# DIDO.net
KiCad netlist of a schematic drawn in Altium Designer
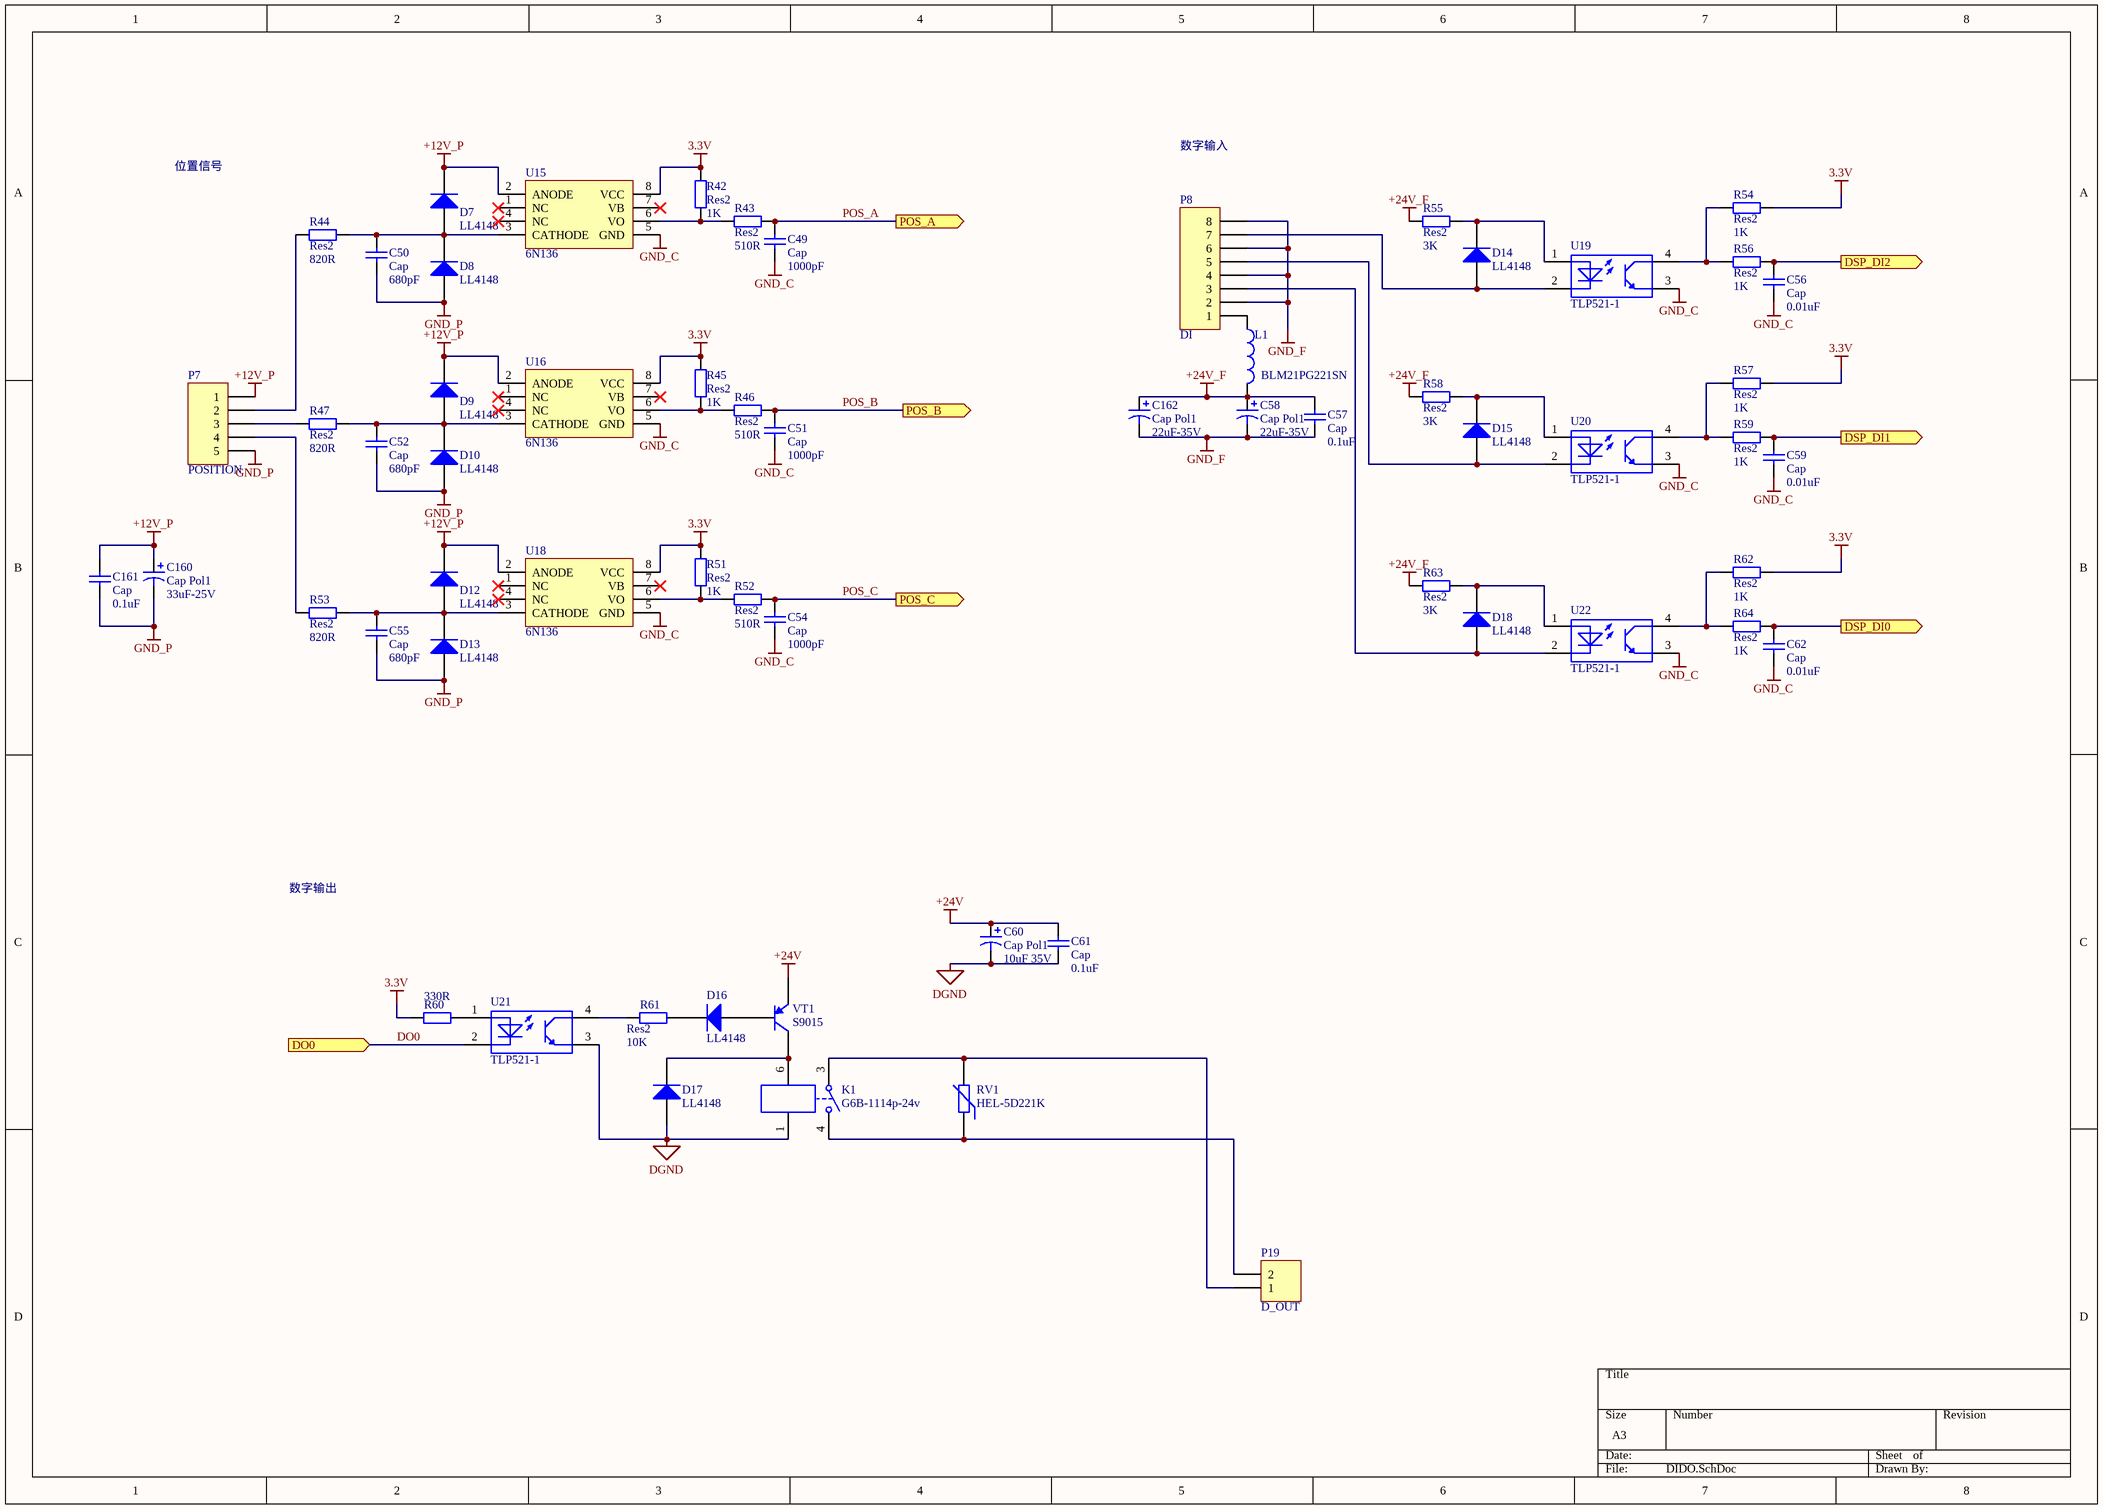
[diagram p0: DIDO.SchDoc]

(export (version "E")
  (design (tool "Eeschema 10.0.6"))
  (components
    (comp (ref "C49")
      (value "Cap")
      (footprint "1206")
      (description "Capacitor")
      (fields (field (name "ALTIUM_VALUE") "1000pF") (field (name "PUBLISHER") "Altium Limited"))
      (libsource (lib "Miscellaneous Devices") (part "Cap"))
    )
    (comp (ref "C50")
      (value "Cap")
      (footprint "1206")
      (description "Capacitor")
      (fields (field (name "ALTIUM_VALUE") "680pF") (field (name "PUBLISHER") "Altium Limited"))
      (libsource (lib "Miscellaneous Devices") (part "Cap"))
    )
    (comp (ref "C51")
      (value "Cap")
      (footprint "1206")
      (description "Capacitor")
      (fields (field (name "ALTIUM_VALUE") "1000pF") (field (name "PUBLISHER") "Altium Limited"))
      (libsource (lib "Miscellaneous Devices") (part "Cap"))
    )
    (comp (ref "C52")
      (value "Cap")
      (footprint "1206")
      (description "Capacitor")
      (fields (field (name "ALTIUM_VALUE") "680pF") (field (name "PUBLISHER") "Altium Limited"))
      (libsource (lib "Miscellaneous Devices") (part "Cap"))
    )
    (comp (ref "C54")
      (value "Cap")
      (footprint "1206")
      (description "Capacitor")
      (fields (field (name "ALTIUM_VALUE") "1000pF") (field (name "PUBLISHER") "Altium Limited"))
      (libsource (lib "Miscellaneous Devices") (part "Cap"))
    )
    (comp (ref "C55")
      (value "Cap")
      (footprint "1206")
      (description "Capacitor")
      (fields (field (name "ALTIUM_VALUE") "680pF") (field (name "PUBLISHER") "Altium Limited"))
      (libsource (lib "Miscellaneous Devices") (part "Cap"))
    )
    (comp (ref "C56")
      (value "Cap")
      (footprint "1206")
      (description "Capacitor")
      (fields (field (name "ALTIUM_VALUE") "0.01uF") (field (name "PUBLISHER") "Altium Limited"))
      (libsource (lib "Miscellaneous Devices") (part "Cap"))
    )
    (comp (ref "C57")
      (value "Cap")
      (footprint "1206")
      (description "Capacitor")
      (fields (field (name "ALTIUM_VALUE") "0.1uF") (field (name "PUBLISHER") "Altium Limited"))
      (libsource (lib "Miscellaneous Devices") (part "Cap"))
    )
    (comp (ref "C58")
      (value "Cap Pol1")
      (footprint "7343")
      (description "Polarized Capacitor (Radial)")
      (fields (field (name "ALTIUM_VALUE") "22uF-35V") (field (name "PUBLISHER") "Altium Limited"))
      (libsource (lib "Miscellaneous Devices") (part "Cap Pol1"))
    )
    (comp (ref "C59")
      (value "Cap")
      (footprint "1206")
      (description "Capacitor")
      (fields (field (name "ALTIUM_VALUE") "0.01uF") (field (name "PUBLISHER") "Altium Limited"))
      (libsource (lib "Miscellaneous Devices") (part "Cap"))
    )
    (comp (ref "C60")
      (value "Cap Pol1")
      (footprint "7343")
      (description "Polarized Capacitor (Radial)")
      (fields (field (name "ALTIUM_VALUE") "10uF 35V") (field (name "PUBLISHER") "Altium Limited"))
      (libsource (lib "Miscellaneous Devices") (part "Cap Pol1"))
    )
    (comp (ref "C61")
      (value "Cap")
      (footprint "1206")
      (description "Capacitor")
      (fields (field (name "ALTIUM_VALUE") "0.1uF") (field (name "PUBLISHER") "Altium Limited"))
      (libsource (lib "Miscellaneous Devices") (part "Cap"))
    )
    (comp (ref "C62")
      (value "Cap")
      (footprint "1206")
      (description "Capacitor")
      (fields (field (name "ALTIUM_VALUE") "0.01uF") (field (name "PUBLISHER") "Altium Limited"))
      (libsource (lib "Miscellaneous Devices") (part "Cap"))
    )
    (comp (ref "C160")
      (value "Cap Pol1")
      (footprint "7343")
      (description "Polarized Capacitor (Radial)")
      (fields (field (name "ALTIUM_VALUE") "33uF-25V") (field (name "PUBLISHER") "Altium Limited"))
      (libsource (lib "Miscellaneous Devices") (part "Cap Pol1"))
    )
    (comp (ref "C161")
      (value "Cap")
      (footprint "1206")
      (description "Capacitor")
      (fields (field (name "ALTIUM_VALUE") "0.1uF") (field (name "PUBLISHER") "Altium Limited"))
      (libsource (lib "Miscellaneous Devices") (part "Cap"))
    )
    (comp (ref "C162")
      (value "Cap Pol1")
      (footprint "7343")
      (description "Polarized Capacitor (Radial)")
      (fields (field (name "ALTIUM_VALUE") "22uF-35V") (field (name "PUBLISHER") "Altium Limited"))
      (libsource (lib "Miscellaneous Devices") (part "Cap Pol1"))
    )
    (comp (ref "D7")
      (value "LL4148")
      (footprint "SOD-80/MLL34")
      (description "High Conductance Fast Diode")
      (fields (field (name "PUBLISHER") "Altium Limited"))
      (libsource (lib "Miscellaneous Devices") (part "Diode 1N4148"))
    )
    (comp (ref "D8")
      (value "LL4148")
      (footprint "SOD-80/MLL34")
      (description "High Conductance Fast Diode")
      (fields (field (name "PUBLISHER") "Altium Limited"))
      (libsource (lib "Miscellaneous Devices") (part "Diode 1N4148"))
    )
    (comp (ref "D9")
      (value "LL4148")
      (footprint "SOD-80/MLL34")
      (description "High Conductance Fast Diode")
      (fields (field (name "PUBLISHER") "Altium Limited"))
      (libsource (lib "Miscellaneous Devices") (part "Diode 1N4148"))
    )
    (comp (ref "D10")
      (value "LL4148")
      (footprint "SOD-80/MLL34")
      (description "High Conductance Fast Diode")
      (fields (field (name "PUBLISHER") "Altium Limited"))
      (libsource (lib "Miscellaneous Devices") (part "Diode 1N4148"))
    )
    (comp (ref "D12")
      (value "LL4148")
      (footprint "SOD-80/MLL34")
      (description "High Conductance Fast Diode")
      (fields (field (name "PUBLISHER") "Altium Limited"))
      (libsource (lib "Miscellaneous Devices") (part "Diode 1N4148"))
    )
    (comp (ref "D13")
      (value "LL4148")
      (footprint "SOD-80/MLL34")
      (description "High Conductance Fast Diode")
      (fields (field (name "PUBLISHER") "Altium Limited"))
      (libsource (lib "Miscellaneous Devices") (part "Diode 1N4148"))
    )
    (comp (ref "D14")
      (value "LL4148")
      (footprint "SOD-80/MLL34")
      (description "1 Amp General Purpose Rectifier")
      (fields (field (name "PUBLISHER") "Altium Limited"))
      (libsource (lib "Miscellaneous Devices") (part "Diode 1N4007"))
    )
    (comp (ref "D15")
      (value "LL4148")
      (footprint "SOD-80/MLL34")
      (description "1 Amp General Purpose Rectifier")
      (fields (field (name "PUBLISHER") "Altium Limited"))
      (libsource (lib "Miscellaneous Devices") (part "Diode 1N4007"))
    )
    (comp (ref "D16")
      (value "LL4148")
      (footprint "SOD-80/MLL34")
      (description "High Conductance Fast Diode")
      (fields (field (name "PUBLISHER") "Altium Limited"))
      (libsource (lib "Miscellaneous Devices") (part "Diode 1N4148"))
    )
    (comp (ref "D17")
      (value "LL4148")
      (footprint "SOD-80/MLL34")
      (description "1 Amp General Purpose Rectifier")
      (fields (field (name "PUBLISHER") "Altium Limited"))
      (libsource (lib "Miscellaneous Devices") (part "Diode 1N4007"))
    )
    (comp (ref "D18")
      (value "LL4148")
      (footprint "SOD-80/MLL34")
      (description "1 Amp General Purpose Rectifier")
      (fields (field (name "PUBLISHER") "Altium Limited"))
      (libsource (lib "Miscellaneous Devices") (part "Diode 1N4007"))
    )
    (comp (ref "K1")
      (value "G6B-1114p-24v")
      (footprint "SPST-NO")
      (description "Single-Pole Single-Throw Relay")
      (fields (field (name "PUBLISHER") "Altium Limited"))
      (libsource (lib "Miscellaneous Devices") (part "Relay-SPST"))
    )
    (comp (ref "L1")
      (value "BLM21PG221SN")
      (footprint "2012")
      (description "Inductor")
      (fields (field (name "PUBLISHER") "Altium Limited"))
      (libsource (lib "Miscellaneous Devices") (part "Inductor"))
    )
    (comp (ref "P7")
      (value "POSITION")
      (footprint "phenox-5")
      (description "Header, 5-Pin")
      (fields (field (name "PUBLISHER") "Altium Limited"))
      (libsource (lib "Miscellaneous Connectors") (part "Header 5"))
    )
    (comp (ref "P8")
      (value "DI")
      (footprint "PCB21:phenox-8")
      (description "Header, 8-Pin")
      (fields (field (name "PUBLISHER") "Altium Limited"))
      (libsource (lib "Miscellaneous Connectors") (part "Header 8"))
    )
    (comp (ref "P19")
      (value "D_OUT")
      (footprint "phenox-2")
      (description "Header, 2-Pin")
      (fields (field (name "PUBLISHER") "Altium Limited"))
      (libsource (lib "Miscellaneous Connectors") (part "Header 2"))
    )
    (comp (ref "R42")
      (value "Res2")
      (footprint "1206")
      (description "Resistor")
      (fields (field (name "ALTIUM_VALUE") "1K") (field (name "PUBLISHER") "Altium Limited"))
      (libsource (lib "") (part "Res2_1"))
    )
    (comp (ref "R43")
      (value "Res2")
      (footprint "1206")
      (description "Resistor")
      (fields (field (name "ALTIUM_VALUE") "510R") (field (name "PUBLISHER") "Altium Limited"))
      (libsource (lib "Miscellaneous Devices") (part "Res2"))
    )
    (comp (ref "R44")
      (value "Res2")
      (footprint "1206")
      (description "Resistor")
      (fields (field (name "ALTIUM_VALUE") "820R") (field (name "PUBLISHER") "Altium Limited"))
      (libsource (lib "Miscellaneous Devices") (part "Res2"))
    )
    (comp (ref "R45")
      (value "Res2")
      (footprint "1206")
      (description "Resistor")
      (fields (field (name "ALTIUM_VALUE") "1K") (field (name "PUBLISHER") "Altium Limited"))
      (libsource (lib "") (part "Res2_1"))
    )
    (comp (ref "R46")
      (value "Res2")
      (footprint "1206")
      (description "Resistor")
      (fields (field (name "ALTIUM_VALUE") "510R") (field (name "PUBLISHER") "Altium Limited"))
      (libsource (lib "Miscellaneous Devices") (part "Res2"))
    )
    (comp (ref "R47")
      (value "Res2")
      (footprint "1206")
      (description "Resistor")
      (fields (field (name "ALTIUM_VALUE") "820R") (field (name "PUBLISHER") "Altium Limited"))
      (libsource (lib "Miscellaneous Devices") (part "Res2"))
    )
    (comp (ref "R51")
      (value "Res2")
      (footprint "1206")
      (description "Resistor")
      (fields (field (name "ALTIUM_VALUE") "1K") (field (name "PUBLISHER") "Altium Limited"))
      (libsource (lib "") (part "Res2_1"))
    )
    (comp (ref "R52")
      (value "Res2")
      (footprint "1206")
      (description "Resistor")
      (fields (field (name "ALTIUM_VALUE") "510R") (field (name "PUBLISHER") "Altium Limited"))
      (libsource (lib "Miscellaneous Devices") (part "Res2"))
    )
    (comp (ref "R53")
      (value "Res2")
      (footprint "1206")
      (description "Resistor")
      (fields (field (name "ALTIUM_VALUE") "820R") (field (name "PUBLISHER") "Altium Limited"))
      (libsource (lib "Miscellaneous Devices") (part "Res2"))
    )
    (comp (ref "R54")
      (value "Res2")
      (footprint "1206")
      (description "Resistor")
      (fields (field (name "ALTIUM_VALUE") "1K") (field (name "PUBLISHER") "Altium Limited"))
      (libsource (lib "Miscellaneous Devices") (part "Res2"))
    )
    (comp (ref "R55")
      (value "Res2")
      (footprint "1206")
      (description "Resistor")
      (fields (field (name "ALTIUM_VALUE") "3K") (field (name "PUBLISHER") "Altium Limited"))
      (libsource (lib "Miscellaneous Devices") (part "Res2"))
    )
    (comp (ref "R56")
      (value "Res2")
      (footprint "1206")
      (description "Resistor")
      (fields (field (name "ALTIUM_VALUE") "1K") (field (name "PUBLISHER") "Altium Limited"))
      (libsource (lib "Miscellaneous Devices") (part "Res2"))
    )
    (comp (ref "R57")
      (value "Res2")
      (footprint "1206")
      (description "Resistor")
      (fields (field (name "ALTIUM_VALUE") "1K") (field (name "PUBLISHER") "Altium Limited"))
      (libsource (lib "Miscellaneous Devices") (part "Res2"))
    )
    (comp (ref "R58")
      (value "Res2")
      (footprint "1206")
      (description "Resistor")
      (fields (field (name "ALTIUM_VALUE") "3K") (field (name "PUBLISHER") "Altium Limited"))
      (libsource (lib "Miscellaneous Devices") (part "Res2"))
    )
    (comp (ref "R59")
      (value "Res2")
      (footprint "1206")
      (description "Resistor")
      (fields (field (name "ALTIUM_VALUE") "1K") (field (name "PUBLISHER") "Altium Limited"))
      (libsource (lib "Miscellaneous Devices") (part "Res2"))
    )
    (comp (ref "R60")
      (value "330R")
      (footprint "1206")
      (description "Resistor")
      (fields (field (name "Comment") "Res2") (field (name "PUBLISHER") "Altium Limited"))
      (libsource (lib "Miscellaneous Devices") (part "Res2"))
    )
    (comp (ref "R61")
      (value "Res2")
      (footprint "1206")
      (description "Resistor")
      (fields (field (name "ALTIUM_VALUE") "10K") (field (name "PUBLISHER") "Altium Limited"))
      (libsource (lib "Miscellaneous Devices") (part "Res2"))
    )
    (comp (ref "R62")
      (value "Res2")
      (footprint "1206")
      (description "Resistor")
      (fields (field (name "ALTIUM_VALUE") "1K") (field (name "PUBLISHER") "Altium Limited"))
      (libsource (lib "Miscellaneous Devices") (part "Res2"))
    )
    (comp (ref "R63")
      (value "Res2")
      (footprint "1206")
      (description "Resistor")
      (fields (field (name "ALTIUM_VALUE") "3K") (field (name "PUBLISHER") "Altium Limited"))
      (libsource (lib "Miscellaneous Devices") (part "Res2"))
    )
    (comp (ref "R64")
      (value "Res2")
      (footprint "1206")
      (description "Resistor")
      (fields (field (name "ALTIUM_VALUE") "1K") (field (name "PUBLISHER") "Altium Limited"))
      (libsource (lib "Miscellaneous Devices") (part "Res2"))
    )
    (comp (ref "RV1")
      (value "HEL-5D221K")
      (footprint "RAD-0.2")
      (libsource (lib "Schlib1") (part "HEL-5D221K"))
    )
    (comp (ref "U15")
      (value "6N136")
      (footprint "DIP-8N")
      (description "光耦")
      (libsource (lib "Integrated_Library1") (part "6N136"))
    )
    (comp (ref "U16")
      (value "6N136")
      (footprint "DIP-8N")
      (description "光耦")
      (libsource (lib "Integrated_Library1") (part "6N136"))
    )
    (comp (ref "U18")
      (value "6N136")
      (footprint "DIP-8N")
      (description "光耦")
      (libsource (lib "Integrated_Library1") (part "6N136"))
    )
    (comp (ref "U19")
      (value "TLP521-1")
      (footprint "DIP4")
      (libsource (lib "Integrated_Library1") (part "TLP521-1"))
    )
    (comp (ref "U20")
      (value "TLP521-1")
      (footprint "DIP4")
      (libsource (lib "Integrated_Library1") (part "TLP521-1"))
    )
    (comp (ref "U21")
      (value "TLP521-1")
      (footprint "DIP4")
      (libsource (lib "Integrated_Library1") (part "TLP521-1"))
    )
    (comp (ref "U22")
      (value "TLP521-1")
      (footprint "DIP4")
      (libsource (lib "Integrated_Library1") (part "TLP521-1"))
    )
    (comp (ref "VT1") (value "S9015") (footprint "SOT23") (libsource (lib "Schlib2") (part "S9015")))
  )
  (nets
    (net (code "1") (name "+12V_P") (class "Default")
      (node (ref "C160") (pin "1") (pinfunction "1_1") (pintype "passive"))
      (node (ref "C161") (pin "2") (pinfunction "2_2") (pintype "passive"))
      (node (ref "D12") (pin "2") (pinfunction "K_2") (pintype "passive"))
      (node (ref "D7") (pin "2") (pinfunction "K_2") (pintype "passive"))
      (node (ref "D9") (pin "2") (pinfunction "K_2") (pintype "passive"))
      (node (ref "P7") (pin "1") (pinfunction "1_1") (pintype "passive"))
      (node (ref "U15") (pin "2") (pinfunction "ANODE_2") (pintype "passive"))
      (node (ref "U16") (pin "2") (pinfunction "ANODE_2") (pintype "passive"))
      (node (ref "U18") (pin "2") (pinfunction "ANODE_2") (pintype "passive"))
    )
    (net (code "2") (name "+24V") (class "Default")
      (node (ref "C60") (pin "1") (pinfunction "1_1") (pintype "passive"))
      (node (ref "C61") (pin "2") (pinfunction "2_2") (pintype "passive"))
      (node (ref "VT1") (pin "3") (pinfunction "3_3") (pintype "passive"))
    )
    (net (code "3") (name "+24V_F") (class "Default")
      (node (ref "C162") (pin "1") (pinfunction "1_1") (pintype "passive"))
      (node (ref "C57") (pin "2") (pinfunction "2_2") (pintype "passive"))
      (node (ref "C58") (pin "1") (pinfunction "1_1") (pintype "passive"))
      (node (ref "L1") (pin "2") (pinfunction "2_2") (pintype "passive"))
      (node (ref "R55") (pin "1") (pinfunction "1_1") (pintype "passive"))
      (node (ref "R58") (pin "1") (pinfunction "1_1") (pintype "passive"))
      (node (ref "R63") (pin "1") (pinfunction "1_1") (pintype "passive"))
    )
    (net (code "4") (name "/DO0") (class "Default")
      (node (ref "U21") (pin "2") (pinfunction "2_2") (pintype "passive"))
    )
    (net (code "5") (name "/DSP_DI0") (class "Default")
      (node (ref "C62") (pin "2") (pinfunction "2_2") (pintype "passive"))
      (node (ref "R64") (pin "2") (pinfunction "2_2") (pintype "passive"))
    )
    (net (code "6") (name "/DSP_DI1") (class "Default")
      (node (ref "C59") (pin "2") (pinfunction "2_2") (pintype "passive"))
      (node (ref "R59") (pin "2") (pinfunction "2_2") (pintype "passive"))
    )
    (net (code "7") (name "/DSP_DI2") (class "Default")
      (node (ref "C56") (pin "2") (pinfunction "2_2") (pintype "passive"))
      (node (ref "R56") (pin "2") (pinfunction "2_2") (pintype "passive"))
    )
    (net (code "8") (name "/POS_A") (class "Default")
      (node (ref "C49") (pin "2") (pinfunction "2_2") (pintype "passive"))
      (node (ref "R43") (pin "2") (pinfunction "2_2") (pintype "passive"))
    )
    (net (code "9") (name "/POS_B") (class "Default")
      (node (ref "C51") (pin "2") (pinfunction "2_2") (pintype "passive"))
      (node (ref "R46") (pin "2") (pinfunction "2_2") (pintype "passive"))
    )
    (net (code "10") (name "/POS_C") (class "Default")
      (node (ref "C54") (pin "2") (pinfunction "2_2") (pintype "passive"))
      (node (ref "R52") (pin "2") (pinfunction "2_2") (pintype "passive"))
    )
    (net (code "11") (name "3.3V") (class "Default")
      (node (ref "R42") (pin "2") (pinfunction "2_2") (pintype "passive"))
      (node (ref "R45") (pin "2") (pinfunction "2_2") (pintype "passive"))
      (node (ref "R51") (pin "2") (pinfunction "2_2") (pintype "passive"))
      (node (ref "R54") (pin "2") (pinfunction "2_2") (pintype "passive"))
      (node (ref "R57") (pin "2") (pinfunction "2_2") (pintype "passive"))
      (node (ref "R60") (pin "1") (pinfunction "1_1") (pintype "passive"))
      (node (ref "R62") (pin "2") (pinfunction "2_2") (pintype "passive"))
      (node (ref "U15") (pin "8") (pinfunction "VCC_8") (pintype "power_in"))
      (node (ref "U16") (pin "8") (pinfunction "VCC_8") (pintype "power_in"))
      (node (ref "U18") (pin "8") (pinfunction "VCC_8") (pintype "power_in"))
    )
    (net (code "12") (name "DGND") (class "Default")
      (node (ref "C60") (pin "2") (pinfunction "2_2") (pintype "passive"))
      (node (ref "C61") (pin "1") (pinfunction "1_1") (pintype "passive"))
      (node (ref "D17") (pin "1") (pinfunction "A_1") (pintype "passive"))
      (node (ref "K1") (pin "1") (pinfunction "1_1") (pintype "passive"))
      (node (ref "U21") (pin "3") (pinfunction "3_3") (pintype "passive"))
    )
    (net (code "13") (name "GND_C") (class "Default")
      (node (ref "C49") (pin "1") (pinfunction "1_1") (pintype "passive"))
      (node (ref "C51") (pin "1") (pinfunction "1_1") (pintype "passive"))
      (node (ref "C54") (pin "1") (pinfunction "1_1") (pintype "passive"))
      (node (ref "C56") (pin "1") (pinfunction "1_1") (pintype "passive"))
      (node (ref "C59") (pin "1") (pinfunction "1_1") (pintype "passive"))
      (node (ref "C62") (pin "1") (pinfunction "1_1") (pintype "passive"))
      (node (ref "U15") (pin "5") (pinfunction "GND_5") (pintype "passive"))
      (node (ref "U16") (pin "5") (pinfunction "GND_5") (pintype "passive"))
      (node (ref "U18") (pin "5") (pinfunction "GND_5") (pintype "passive"))
      (node (ref "U19") (pin "3") (pinfunction "3_3") (pintype "passive"))
      (node (ref "U20") (pin "3") (pinfunction "3_3") (pintype "passive"))
      (node (ref "U22") (pin "3") (pinfunction "3_3") (pintype "passive"))
    )
    (net (code "14") (name "GND_F") (class "Default")
      (node (ref "C162") (pin "2") (pinfunction "2_2") (pintype "passive"))
      (node (ref "C57") (pin "1") (pinfunction "1_1") (pintype "passive"))
      (node (ref "C58") (pin "2") (pinfunction "2_2") (pintype "passive"))
      (node (ref "P8") (pin "2") (pinfunction "2_2") (pintype "passive"))
      (node (ref "P8") (pin "4") (pinfunction "4_4") (pintype "passive"))
      (node (ref "P8") (pin "6") (pinfunction "6_6") (pintype "passive"))
      (node (ref "P8") (pin "8") (pinfunction "8_8") (pintype "passive"))
    )
    (net (code "15") (name "GND_P") (class "Default")
      (node (ref "C160") (pin "2") (pinfunction "2_2") (pintype "passive"))
      (node (ref "C161") (pin "1") (pinfunction "1_1") (pintype "passive"))
      (node (ref "C50") (pin "1") (pinfunction "1_1") (pintype "passive"))
      (node (ref "C52") (pin "1") (pinfunction "1_1") (pintype "passive"))
      (node (ref "C55") (pin "1") (pinfunction "1_1") (pintype "passive"))
      (node (ref "D10") (pin "1") (pinfunction "A_1") (pintype "passive"))
      (node (ref "D13") (pin "1") (pinfunction "A_1") (pintype "passive"))
      (node (ref "D8") (pin "1") (pinfunction "A_1") (pintype "passive"))
      (node (ref "P7") (pin "5") (pinfunction "5_5") (pintype "passive"))
    )
    (net (code "16") (name "Net-(D7-A)") (class "Default")
      (node (ref "C50") (pin "2") (pinfunction "2_2") (pintype "passive"))
      (node (ref "D7") (pin "1") (pinfunction "A_1") (pintype "passive"))
      (node (ref "D8") (pin "2") (pinfunction "K_2") (pintype "passive"))
      (node (ref "R44") (pin "2") (pinfunction "2_2") (pintype "passive"))
      (node (ref "U15") (pin "3") (pinfunction "CATHODE_3") (pintype "passive"))
    )
    (net (code "17") (name "Net-(D10-K)") (class "Default")
      (node (ref "C52") (pin "2") (pinfunction "2_2") (pintype "passive"))
      (node (ref "D10") (pin "2") (pinfunction "K_2") (pintype "passive"))
      (node (ref "D9") (pin "1") (pinfunction "A_1") (pintype "passive"))
      (node (ref "R47") (pin "2") (pinfunction "2_2") (pintype "passive"))
      (node (ref "U16") (pin "3") (pinfunction "CATHODE_3") (pintype "passive"))
    )
    (net (code "18") (name "Net-(D12-A)") (class "Default")
      (node (ref "C55") (pin "2") (pinfunction "2_2") (pintype "passive"))
      (node (ref "D12") (pin "1") (pinfunction "A_1") (pintype "passive"))
      (node (ref "D13") (pin "2") (pinfunction "K_2") (pintype "passive"))
      (node (ref "R53") (pin "2") (pinfunction "2_2") (pintype "passive"))
      (node (ref "U18") (pin "3") (pinfunction "CATHODE_3") (pintype "passive"))
    )
    (net (code "19") (name "Net-(D14-A)") (class "Default")
      (node (ref "D14") (pin "1") (pinfunction "A_1") (pintype "passive"))
      (node (ref "P8") (pin "7") (pinfunction "7_7") (pintype "passive"))
      (node (ref "U19") (pin "2") (pinfunction "2_2") (pintype "passive"))
    )
    (net (code "20") (name "Net-(D14-K)") (class "Default")
      (node (ref "D14") (pin "2") (pinfunction "K_2") (pintype "passive"))
      (node (ref "R55") (pin "2") (pinfunction "2_2") (pintype "passive"))
      (node (ref "U19") (pin "1") (pinfunction "1_1") (pintype "passive"))
    )
    (net (code "21") (name "Net-(D15-A)") (class "Default")
      (node (ref "D15") (pin "1") (pinfunction "A_1") (pintype "passive"))
      (node (ref "P8") (pin "5") (pinfunction "5_5") (pintype "passive"))
      (node (ref "U20") (pin "2") (pinfunction "2_2") (pintype "passive"))
    )
    (net (code "22") (name "Net-(D15-K)") (class "Default")
      (node (ref "D15") (pin "2") (pinfunction "K_2") (pintype "passive"))
      (node (ref "R58") (pin "2") (pinfunction "2_2") (pintype "passive"))
      (node (ref "U20") (pin "1") (pinfunction "1_1") (pintype "passive"))
    )
    (net (code "23") (name "Net-(D16-A)") (class "Default")
      (node (ref "D16") (pin "1") (pinfunction "A_1") (pintype "passive"))
      (node (ref "VT1") (pin "2") (pinfunction "2_2") (pintype "passive"))
    )
    (net (code "24") (name "Net-(D16-K)") (class "Default")
      (node (ref "D16") (pin "2") (pinfunction "K_2") (pintype "passive"))
      (node (ref "R61") (pin "2") (pinfunction "2_2") (pintype "passive"))
    )
    (net (code "25") (name "Net-(D17-K)") (class "Default")
      (node (ref "D17") (pin "2") (pinfunction "K_2") (pintype "passive"))
      (node (ref "K1") (pin "6") (pinfunction "6_6") (pintype "passive"))
      (node (ref "VT1") (pin "1") (pinfunction "1_1") (pintype "passive"))
    )
    (net (code "26") (name "Net-(D18-A)") (class "Default")
      (node (ref "D18") (pin "1") (pinfunction "A_1") (pintype "passive"))
      (node (ref "P8") (pin "3") (pinfunction "3_3") (pintype "passive"))
      (node (ref "U22") (pin "2") (pinfunction "2_2") (pintype "passive"))
    )
    (net (code "27") (name "Net-(D18-K)") (class "Default")
      (node (ref "D18") (pin "2") (pinfunction "K_2") (pintype "passive"))
      (node (ref "R63") (pin "2") (pinfunction "2_2") (pintype "passive"))
      (node (ref "U22") (pin "1") (pinfunction "1_1") (pintype "passive"))
    )
    (net (code "28") (name "Net-(K1-Pad3)") (class "Default")
      (node (ref "K1") (pin "3") (pinfunction "3_3") (pintype "passive"))
      (node (ref "P19") (pin "1") (pinfunction "1_1") (pintype "passive"))
      (node (ref "RV1") (pin "2") (pinfunction "2_2") (pintype "passive"))
    )
    (net (code "29") (name "Net-(K1-Pad4)") (class "Default")
      (node (ref "K1") (pin "4") (pinfunction "4_4") (pintype "passive"))
      (node (ref "P19") (pin "2") (pinfunction "2_2") (pintype "passive"))
      (node (ref "RV1") (pin "1") (pinfunction "1_1") (pintype "passive"))
    )
    (net (code "30") (name "Net-(L1-Pad1)") (class "Default")
      (node (ref "L1") (pin "1") (pinfunction "1_1") (pintype "passive"))
      (node (ref "P8") (pin "1") (pinfunction "1_1") (pintype "passive"))
    )
    (net (code "31") (name "Net-(P7-Pad2)") (class "Default")
      (node (ref "P7") (pin "2") (pinfunction "2_2") (pintype "passive"))
      (node (ref "R44") (pin "1") (pinfunction "1_1") (pintype "passive"))
    )
    (net (code "32") (name "Net-(P7-Pad3)") (class "Default")
      (node (ref "P7") (pin "3") (pinfunction "3_3") (pintype "passive"))
      (node (ref "R47") (pin "1") (pinfunction "1_1") (pintype "passive"))
    )
    (net (code "33") (name "Net-(P7-Pad4)") (class "Default")
      (node (ref "P7") (pin "4") (pinfunction "4_4") (pintype "passive"))
      (node (ref "R53") (pin "1") (pinfunction "1_1") (pintype "passive"))
    )
    (net (code "34") (name "Net-(R54-Pad1)") (class "Default")
      (node (ref "R54") (pin "1") (pinfunction "1_1") (pintype "passive"))
      (node (ref "R56") (pin "1") (pinfunction "1_1") (pintype "passive"))
      (node (ref "U19") (pin "4") (pinfunction "4_4") (pintype "passive"))
    )
    (net (code "35") (name "Net-(R57-Pad1)") (class "Default")
      (node (ref "R57") (pin "1") (pinfunction "1_1") (pintype "passive"))
      (node (ref "R59") (pin "1") (pinfunction "1_1") (pintype "passive"))
      (node (ref "U20") (pin "4") (pinfunction "4_4") (pintype "passive"))
    )
    (net (code "36") (name "Net-(R60-Pad2)") (class "Default")
      (node (ref "R60") (pin "2") (pinfunction "2_2") (pintype "passive"))
      (node (ref "U21") (pin "1") (pinfunction "1_1") (pintype "passive"))
    )
    (net (code "37") (name "Net-(R61-Pad1)") (class "Default")
      (node (ref "R61") (pin "1") (pinfunction "1_1") (pintype "passive"))
      (node (ref "U21") (pin "4") (pinfunction "4_4") (pintype "passive"))
    )
    (net (code "38") (name "Net-(R62-Pad1)") (class "Default")
      (node (ref "R62") (pin "1") (pinfunction "1_1") (pintype "passive"))
      (node (ref "R64") (pin "1") (pinfunction "1_1") (pintype "passive"))
      (node (ref "U22") (pin "4") (pinfunction "4_4") (pintype "passive"))
    )
    (net (code "39") (name "Net-(U15-VO)") (class "Default")
      (node (ref "R42") (pin "1") (pinfunction "1_1") (pintype "passive"))
      (node (ref "R43") (pin "1") (pinfunction "1_1") (pintype "passive"))
      (node (ref "U15") (pin "6") (pinfunction "VO_6") (pintype "passive"))
    )
    (net (code "40") (name "Net-(U16-VO)") (class "Default")
      (node (ref "R45") (pin "1") (pinfunction "1_1") (pintype "passive"))
      (node (ref "R46") (pin "1") (pinfunction "1_1") (pintype "passive"))
      (node (ref "U16") (pin "6") (pinfunction "VO_6") (pintype "passive"))
    )
    (net (code "41") (name "Net-(U18-VO)") (class "Default")
      (node (ref "R51") (pin "1") (pinfunction "1_1") (pintype "passive"))
      (node (ref "R52") (pin "1") (pinfunction "1_1") (pintype "passive"))
      (node (ref "U18") (pin "6") (pinfunction "VO_6") (pintype "passive"))
    )
    (net (code "42") (name "unconnected-(U15-NC-Pad1)") (class "Default")
      (node (ref "U15") (pin "1") (pinfunction "NC_1") (pintype "passive+no_connect"))
    )
    (net (code "43") (name "unconnected-(U15-NC-Pad4)") (class "Default")
      (node (ref "U15") (pin "4") (pinfunction "NC_4") (pintype "power_in+no_connect"))
    )
    (net (code "44") (name "unconnected-(U15-VB-Pad7)") (class "Default")
      (node (ref "U15") (pin "7") (pinfunction "VB_7") (pintype "passive+no_connect"))
    )
    (net (code "45") (name "unconnected-(U16-NC-Pad1)") (class "Default")
      (node (ref "U16") (pin "1") (pinfunction "NC_1") (pintype "passive+no_connect"))
    )
    (net (code "46") (name "unconnected-(U16-NC-Pad4)") (class "Default")
      (node (ref "U16") (pin "4") (pinfunction "NC_4") (pintype "power_in+no_connect"))
    )
    (net (code "47") (name "unconnected-(U16-VB-Pad7)") (class "Default")
      (node (ref "U16") (pin "7") (pinfunction "VB_7") (pintype "passive+no_connect"))
    )
    (net (code "48") (name "unconnected-(U18-NC-Pad1)") (class "Default")
      (node (ref "U18") (pin "1") (pinfunction "NC_1") (pintype "passive+no_connect"))
    )
    (net (code "49") (name "unconnected-(U18-NC-Pad4)") (class "Default")
      (node (ref "U18") (pin "4") (pinfunction "NC_4") (pintype "power_in+no_connect"))
    )
    (net (code "50") (name "unconnected-(U18-VB-Pad7)") (class "Default")
      (node (ref "U18") (pin "7") (pinfunction "VB_7") (pintype "passive+no_connect"))
    )
  )
)
